# THERMAL_MANAGEMENT.net
KiCad netlist of a schematic drawn in Altium Designer
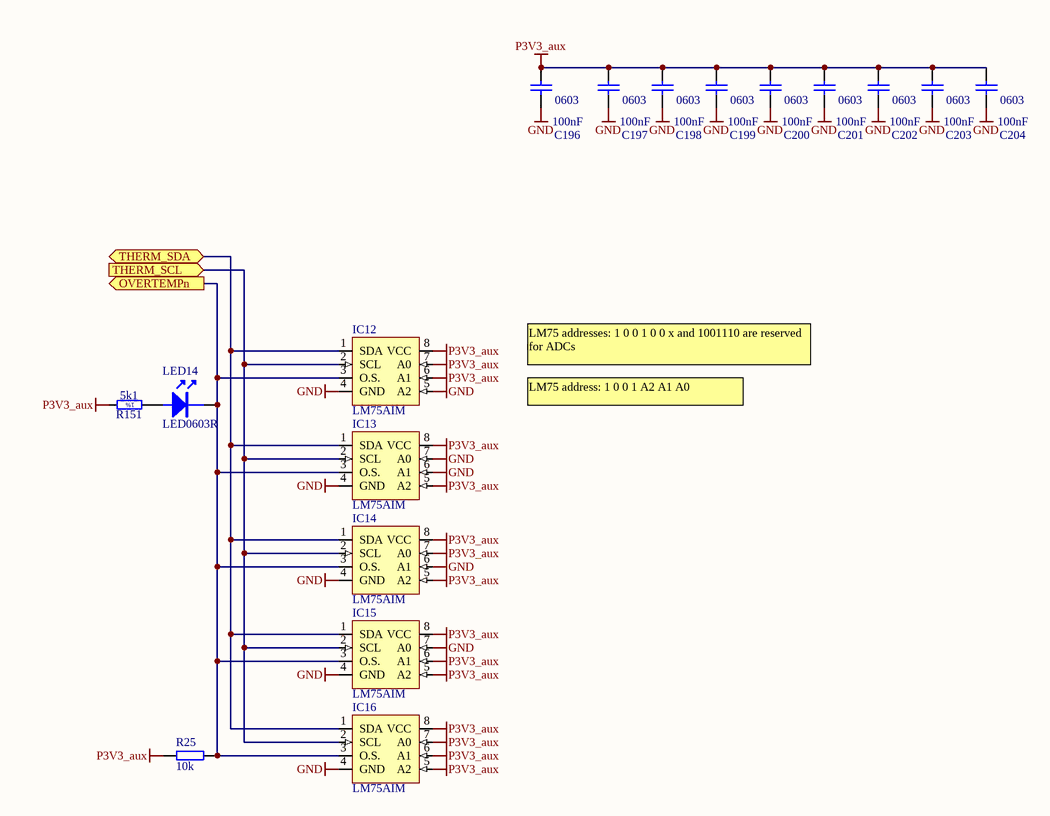
[diagram p0: THERMAL_MANAGEMENT.SchDoc]

(export (version "E")
  (design (tool "Eeschema 10.0.6"))
  (components
    (comp (ref "C196")
      (value "100nF")
      (footprint "0402C")
      (description "Non-polarised capacitor")
      (fields
        (field (name "PART NUMBER") "CC0603_100NF_50V_10%_X7R")
        (field (name "VOLTAGE") "50V")
        (field (name "CASE") "0603")
        (field (name "AUTHOR") "CERN DEM JLC")
      )
      (libsource (lib "Capacitors") (part "Capacitor - non polarized"))
    )
    (comp (ref "C197")
      (value "100nF")
      (footprint "0402C")
      (description "Non-polarised capacitor")
      (fields
        (field (name "PART NUMBER") "CC0603_100NF_50V_10%_X7R")
        (field (name "VOLTAGE") "50V")
        (field (name "CASE") "0603")
        (field (name "AUTHOR") "CERN DEM JLC")
      )
      (libsource (lib "Capacitors") (part "Capacitor - non polarized"))
    )
    (comp (ref "C198")
      (value "100nF")
      (footprint "0402C")
      (description "Non-polarised capacitor")
      (fields
        (field (name "PART NUMBER") "CC0603_100NF_50V_10%_X7R")
        (field (name "VOLTAGE") "50V")
        (field (name "CASE") "0603")
        (field (name "AUTHOR") "CERN DEM JLC")
      )
      (libsource (lib "Capacitors") (part "Capacitor - non polarized"))
    )
    (comp (ref "C199")
      (value "100nF")
      (footprint "0402C")
      (description "Non-polarised capacitor")
      (fields
        (field (name "PART NUMBER") "CC0603_100NF_50V_10%_X7R")
        (field (name "VOLTAGE") "50V")
        (field (name "CASE") "0603")
        (field (name "AUTHOR") "CERN DEM JLC")
      )
      (libsource (lib "Capacitors") (part "Capacitor - non polarized"))
    )
    (comp (ref "C200")
      (value "100nF")
      (footprint "0402C")
      (description "Non-polarised capacitor")
      (fields
        (field (name "PART NUMBER") "CC0603_100NF_50V_10%_X7R")
        (field (name "VOLTAGE") "50V")
        (field (name "CASE") "0603")
        (field (name "AUTHOR") "CERN DEM JLC")
      )
      (libsource (lib "Capacitors") (part "Capacitor - non polarized"))
    )
    (comp (ref "C201")
      (value "100nF")
      (footprint "0402C")
      (description "Non-polarised capacitor")
      (fields
        (field (name "PART NUMBER") "CC0603_100NF_50V_10%_X7R")
        (field (name "VOLTAGE") "50V")
        (field (name "CASE") "0603")
        (field (name "AUTHOR") "CERN DEM JLC")
      )
      (libsource (lib "Capacitors") (part "Capacitor - non polarized"))
    )
    (comp (ref "C202")
      (value "100nF")
      (footprint "0402C")
      (description "Non-polarised capacitor")
      (fields
        (field (name "PART NUMBER") "CC0603_100NF_50V_10%_X7R")
        (field (name "VOLTAGE") "50V")
        (field (name "CASE") "0603")
        (field (name "AUTHOR") "CERN DEM JLC")
      )
      (libsource (lib "Capacitors") (part "Capacitor - non polarized"))
    )
    (comp (ref "C203")
      (value "100nF")
      (footprint "0402C")
      (description "Non-polarised capacitor")
      (fields
        (field (name "PART NUMBER") "CC0603_100NF_50V_10%_X7R")
        (field (name "VOLTAGE") "50V")
        (field (name "CASE") "0603")
        (field (name "AUTHOR") "CERN DEM JLC")
      )
      (libsource (lib "Capacitors") (part "Capacitor - non polarized"))
    )
    (comp (ref "C204")
      (value "100nF")
      (footprint "0402C")
      (description "Non-polarised capacitor")
      (fields
        (field (name "PART NUMBER") "CC0603_100NF_50V_10%_X7R")
        (field (name "VOLTAGE") "50V")
        (field (name "CASE") "0603")
        (field (name "AUTHOR") "CERN DEM JLC")
      )
      (libsource (lib "Capacitors") (part "Capacitor - non polarized"))
    )
    (comp (ref "IC12")
      (value "LM75AIM")
      (footprint "SOIC127P600X175-8N")
      (description "I2C temperature sensor")
      (libsource (lib "LIBRARY_SCH") (part "SENS_LM75"))
    )
    (comp (ref "IC13")
      (value "LM75AIM")
      (footprint "SOIC127P600X175-8N")
      (description "I2C temperature sensor")
      (libsource (lib "LIBRARY_SCH") (part "SENS_LM75"))
    )
    (comp (ref "IC14")
      (value "LM75AIM")
      (footprint "SOIC127P600X175-8N")
      (description "I2C temperature sensor")
      (libsource (lib "LIBRARY_SCH") (part "SENS_LM75"))
    )
    (comp (ref "IC15")
      (value "LM75AIM")
      (footprint "SOIC127P600X175-8N")
      (description "I2C temperature sensor")
      (libsource (lib "LIBRARY_SCH") (part "SENS_LM75"))
    )
    (comp (ref "IC16")
      (value "LM75AIM")
      (footprint "SOIC127P600X175-8N")
      (description "I2C temperature sensor")
      (libsource (lib "LIBRARY_SCH") (part "SENS_LM75"))
    )
    (comp (ref "LED14")
      (value "LED0603R")
      (footprint "led_0603")
      (description "LED")
      (libsource (lib "LIBRARY_SCH") (part "LED_SMD"))
    )
    (comp (ref "R25")
      (value "10k")
      (footprint "0402R")
      (description "SMD Resistor")
      (libsource (lib "*") (part "RES_SMD"))
    )
    (comp (ref "R151")
      (value "5k1")
      (footprint "0603R")
      (description "Resistor - 1%")
      (fields
        (field (name "PART NUMBER") "R0603_5K1_1%_0.1W_100PPM")
        (field (name "POWER") "0.1W")
        (field (name "AUTHOR") "CERN DEM JLC")
      )
      (libsource (lib "Resistors") (part "Resistor - 1%"))
    )
  )
  (nets
    (net (code "1") (name "/OVERTEMPn") (class "Default")
      (node (ref "IC12") (pin "3") (pinfunction "O.S._3") (pintype "open_collector"))
      (node (ref "IC13") (pin "3") (pinfunction "O.S._3") (pintype "open_collector"))
      (node (ref "IC14") (pin "3") (pinfunction "O.S._3") (pintype "open_collector"))
      (node (ref "IC15") (pin "3") (pinfunction "O.S._3") (pintype "open_collector"))
      (node (ref "IC16") (pin "3") (pinfunction "O.S._3") (pintype "open_collector"))
      (node (ref "LED14") (pin "K") (pinfunction "K_K") (pintype "passive"))
      (node (ref "R25") (pin "2") (pinfunction "2_2") (pintype "passive"))
    )
    (net (code "2") (name "/THERM_SCL") (class "Default")
      (node (ref "IC12") (pin "2") (pinfunction "SCL_2") (pintype "input"))
      (node (ref "IC13") (pin "2") (pinfunction "SCL_2") (pintype "input"))
      (node (ref "IC14") (pin "2") (pinfunction "SCL_2") (pintype "input"))
      (node (ref "IC15") (pin "2") (pinfunction "SCL_2") (pintype "input"))
      (node (ref "IC16") (pin "2") (pinfunction "SCL_2") (pintype "input"))
    )
    (net (code "3") (name "/THERM_SDA") (class "Default")
      (node (ref "IC12") (pin "1") (pinfunction "SDA_1") (pintype "bidirectional"))
      (node (ref "IC13") (pin "1") (pinfunction "SDA_1") (pintype "bidirectional"))
      (node (ref "IC14") (pin "1") (pinfunction "SDA_1") (pintype "bidirectional"))
      (node (ref "IC15") (pin "1") (pinfunction "SDA_1") (pintype "bidirectional"))
      (node (ref "IC16") (pin "1") (pinfunction "SDA_1") (pintype "bidirectional"))
    )
    (net (code "4") (name "GND") (class "Default")
      (node (ref "C196") (pin "2") (pinfunction "2_2") (pintype "passive"))
      (node (ref "C197") (pin "2") (pinfunction "2_2") (pintype "passive"))
      (node (ref "C198") (pin "2") (pinfunction "2_2") (pintype "passive"))
      (node (ref "C199") (pin "2") (pinfunction "2_2") (pintype "passive"))
      (node (ref "C200") (pin "2") (pinfunction "2_2") (pintype "passive"))
      (node (ref "C201") (pin "2") (pinfunction "2_2") (pintype "passive"))
      (node (ref "C202") (pin "2") (pinfunction "2_2") (pintype "passive"))
      (node (ref "C203") (pin "2") (pinfunction "2_2") (pintype "passive"))
      (node (ref "C204") (pin "2") (pinfunction "2_2") (pintype "passive"))
      (node (ref "IC12") (pin "4") (pinfunction "GND_4") (pintype "power_in"))
      (node (ref "IC12") (pin "5") (pinfunction "A2_5") (pintype "input"))
      (node (ref "IC13") (pin "4") (pinfunction "GND_4") (pintype "power_in"))
      (node (ref "IC13") (pin "6") (pinfunction "A1_6") (pintype "input"))
      (node (ref "IC13") (pin "7") (pinfunction "A0_7") (pintype "input"))
      (node (ref "IC14") (pin "4") (pinfunction "GND_4") (pintype "power_in"))
      (node (ref "IC14") (pin "6") (pinfunction "A1_6") (pintype "input"))
      (node (ref "IC15") (pin "4") (pinfunction "GND_4") (pintype "power_in"))
      (node (ref "IC15") (pin "7") (pinfunction "A0_7") (pintype "input"))
      (node (ref "IC16") (pin "4") (pinfunction "GND_4") (pintype "power_in"))
    )
    (net (code "5") (name "Net-(LED14-PadA)") (class "Default")
      (node (ref "LED14") (pin "A") (pinfunction "A_A") (pintype "passive"))
      (node (ref "R151") (pin "1") (pinfunction "1_1") (pintype "passive"))
    )
    (net (code "6") (name "P3V3_aux") (class "Default")
      (node (ref "C196") (pin "1") (pinfunction "1_1") (pintype "passive"))
      (node (ref "C197") (pin "1") (pinfunction "1_1") (pintype "passive"))
      (node (ref "C198") (pin "1") (pinfunction "1_1") (pintype "passive"))
      (node (ref "C199") (pin "1") (pinfunction "1_1") (pintype "passive"))
      (node (ref "C200") (pin "1") (pinfunction "1_1") (pintype "passive"))
      (node (ref "C201") (pin "1") (pinfunction "1_1") (pintype "passive"))
      (node (ref "C202") (pin "1") (pinfunction "1_1") (pintype "passive"))
      (node (ref "C203") (pin "1") (pinfunction "1_1") (pintype "passive"))
      (node (ref "C204") (pin "1") (pinfunction "1_1") (pintype "passive"))
      (node (ref "IC12") (pin "6") (pinfunction "A1_6") (pintype "input"))
      (node (ref "IC12") (pin "7") (pinfunction "A0_7") (pintype "input"))
      (node (ref "IC12") (pin "8") (pinfunction "VCC_8") (pintype "power_in"))
      (node (ref "IC13") (pin "5") (pinfunction "A2_5") (pintype "input"))
      (node (ref "IC13") (pin "8") (pinfunction "VCC_8") (pintype "power_in"))
      (node (ref "IC14") (pin "5") (pinfunction "A2_5") (pintype "input"))
      (node (ref "IC14") (pin "7") (pinfunction "A0_7") (pintype "input"))
      (node (ref "IC14") (pin "8") (pinfunction "VCC_8") (pintype "power_in"))
      (node (ref "IC15") (pin "5") (pinfunction "A2_5") (pintype "input"))
      (node (ref "IC15") (pin "6") (pinfunction "A1_6") (pintype "input"))
      (node (ref "IC15") (pin "8") (pinfunction "VCC_8") (pintype "power_in"))
      (node (ref "IC16") (pin "5") (pinfunction "A2_5") (pintype "input"))
      (node (ref "IC16") (pin "6") (pinfunction "A1_6") (pintype "input"))
      (node (ref "IC16") (pin "7") (pinfunction "A0_7") (pintype "input"))
      (node (ref "IC16") (pin "8") (pinfunction "VCC_8") (pintype "power_in"))
      (node (ref "R151") (pin "2") (pinfunction "2_2") (pintype "passive"))
      (node (ref "R25") (pin "1") (pinfunction "1_1") (pintype "passive"))
    )
  )
)
